# m219-bluetooth-input.net
KiCad netlist of a schematic drawn in EAGLE
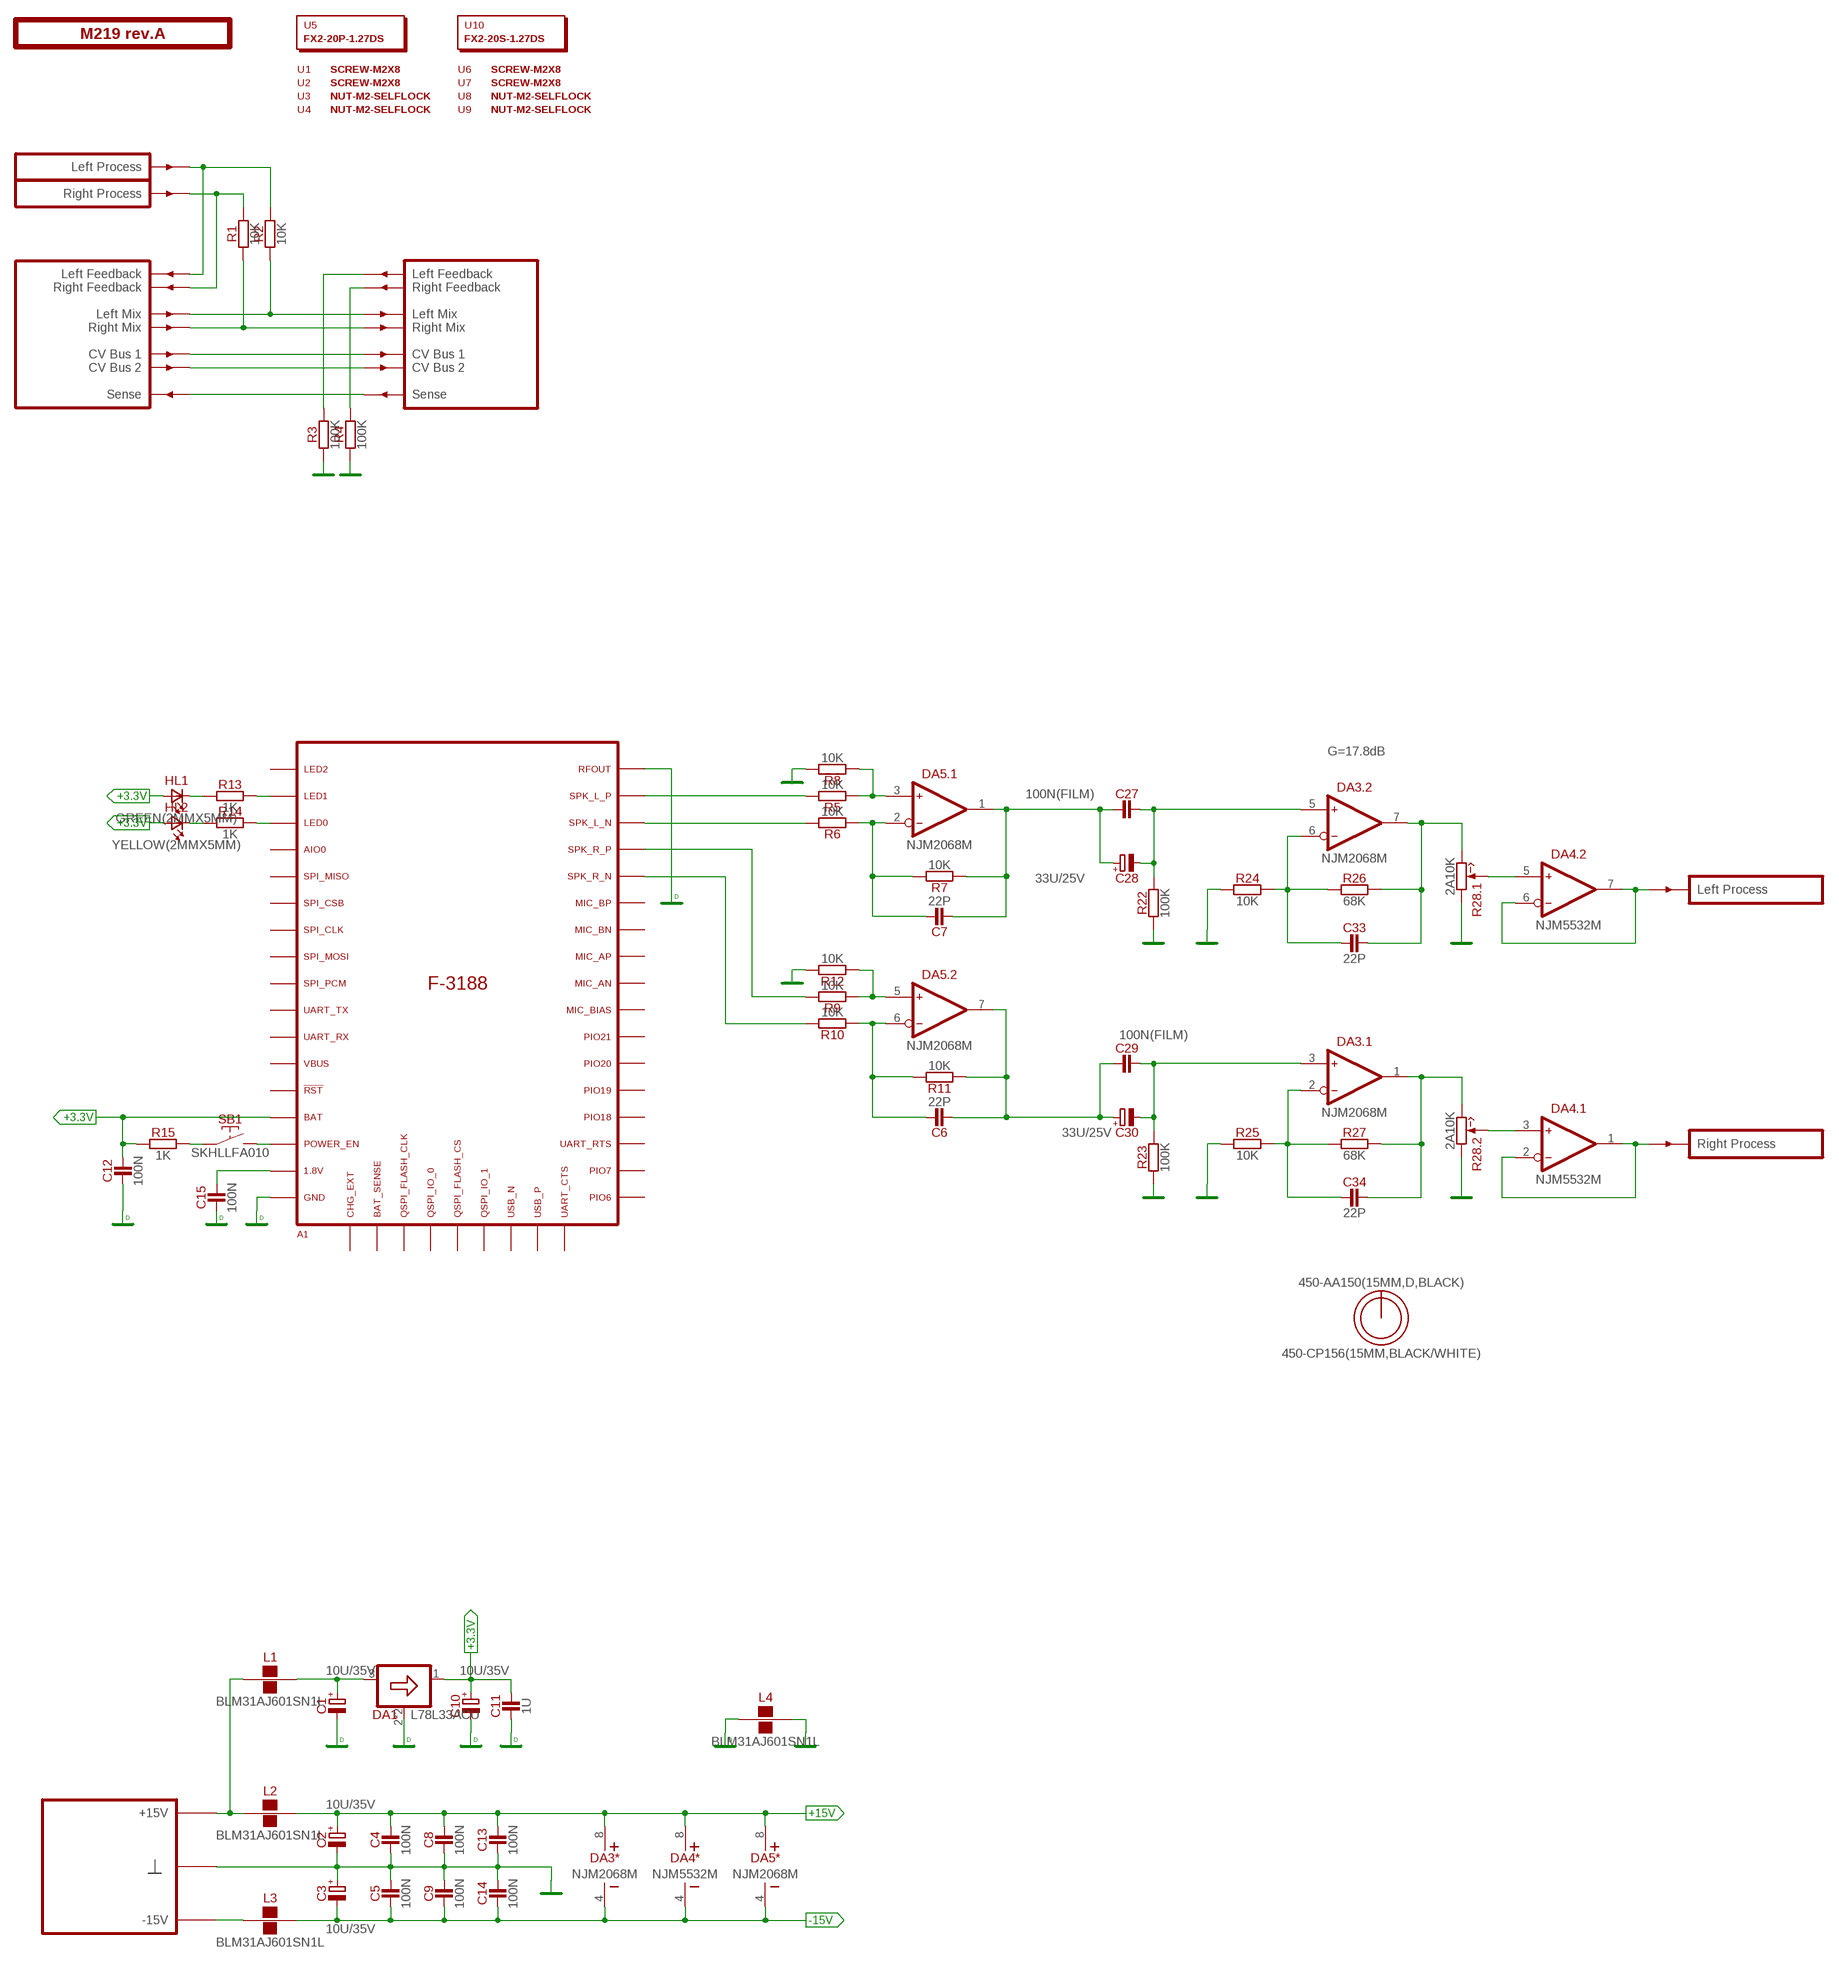
[diagram p0: schematic, sheet 1]

(export (version "E")
  (design (tool "Eeschema 10.0.6"))
  (components
    (comp (ref "A1")
      (value "F3188")
      (footprint "eagle-import:F3188")
      (libsource (lib "eagle-import") (part "F3188"))
    )
    (comp (ref "C1")
      (value "10U/35V")
      (footprint "eagle-import:E2-5")
      (libsource (lib "eagle-import") (part "?10U/35V"))
    )
    (comp (ref "C2")
      (value "10U/35V")
      (footprint "eagle-import:E2-5")
      (libsource (lib "eagle-import") (part "?10U/35V"))
    )
    (comp (ref "C3")
      (value "10U/35V")
      (footprint "eagle-import:E2-5")
      (libsource (lib "eagle-import") (part "?10U/35V"))
    )
    (comp (ref "C4")
      (value "100N")
      (footprint "eagle-import:C-0805")
      (libsource (lib "eagle-import") (part "?100N"))
    )
    (comp (ref "C5")
      (value "100N")
      (footprint "eagle-import:C-0805")
      (libsource (lib "eagle-import") (part "?100N"))
    )
    (comp (ref "C6")
      (value "22P")
      (footprint "eagle-import:C-0805")
      (libsource (lib "eagle-import") (part "?22P"))
    )
    (comp (ref "C7")
      (value "22P")
      (footprint "eagle-import:C-0805")
      (libsource (lib "eagle-import") (part "?22P"))
    )
    (comp (ref "C8")
      (value "100N")
      (footprint "eagle-import:C-0805")
      (libsource (lib "eagle-import") (part "?100N"))
    )
    (comp (ref "C9")
      (value "100N")
      (footprint "eagle-import:C-0805")
      (libsource (lib "eagle-import") (part "?100N"))
    )
    (comp (ref "C10")
      (value "10U/35V")
      (footprint "eagle-import:E2-5")
      (libsource (lib "eagle-import") (part "?10U/35V"))
    )
    (comp (ref "C11")
      (value "1U")
      (footprint "eagle-import:C-0805")
      (libsource (lib "eagle-import") (part "?1U"))
    )
    (comp (ref "C12")
      (value "100N")
      (footprint "eagle-import:C-0805")
      (libsource (lib "eagle-import") (part "?100N"))
    )
    (comp (ref "C13")
      (value "100N")
      (footprint "eagle-import:C-0805")
      (libsource (lib "eagle-import") (part "?100N"))
    )
    (comp (ref "C14")
      (value "100N")
      (footprint "eagle-import:C-0805")
      (libsource (lib "eagle-import") (part "?100N"))
    )
    (comp (ref "C15")
      (value "100N")
      (footprint "eagle-import:C-0805")
      (libsource (lib "eagle-import") (part "?100N"))
    )
    (comp (ref "C27")
      (value "100N(FILM)")
      (footprint "eagle-import:C050-025X075")
      (libsource (lib "eagle-import") (part "?100N(FILM)"))
    )
    (comp (ref "C28")
      (value "33U/25V")
      (footprint "eagle-import:E2,5-7")
      (libsource (lib "eagle-import") (part "?33U/25V"))
    )
    (comp (ref "C29")
      (value "100N(FILM)")
      (footprint "eagle-import:C050-025X075")
      (libsource (lib "eagle-import") (part "?100N(FILM)"))
    )
    (comp (ref "C30")
      (value "33U/25V")
      (footprint "eagle-import:E2,5-7")
      (libsource (lib "eagle-import") (part "?33U/25V"))
    )
    (comp (ref "C33")
      (value "22P")
      (footprint "eagle-import:C-0805")
      (libsource (lib "eagle-import") (part "?22P"))
    )
    (comp (ref "C34")
      (value "22P")
      (footprint "eagle-import:C-0805")
      (libsource (lib "eagle-import") (part "?22P"))
    )
    (comp (ref "DA1")
      (value "L78L33ACU")
      (footprint "eagle-import:SOT89")
      (libsource (lib "eagle-import") (part "?L78L33ACU"))
    )
    (comp (ref "DA3")
      (value "NJM2068M")
      (footprint "eagle-import:SO-8")
      (libsource (lib "eagle-import") (part "NJM2068M"))
    )
    (comp (ref "DA4")
      (value "NJM5532M")
      (footprint "eagle-import:SO-8")
      (libsource (lib "eagle-import") (part "NJM5532M"))
    )
    (comp (ref "DA5")
      (value "NJM2068M")
      (footprint "eagle-import:SO-8")
      (libsource (lib "eagle-import") (part "NJM2068M"))
    )
    (comp (ref "HL1")
      (value "GREEN(2MMX5MM)")
      (footprint "eagle-import:LED2X5")
      (libsource (lib "eagle-import") (part "?(2MMX5MM)GREEN"))
    )
    (comp (ref "HL2")
      (value "YELLOW(2MMX5MM)")
      (footprint "eagle-import:LED2X5")
      (libsource (lib "eagle-import") (part "?(2MMX5MM)YELLOW"))
    )
    (comp (ref "L1")
      (value "BLM31AJ601SN1L")
      (footprint "eagle-import:1206")
      (libsource (lib "eagle-import") (part "BLM31AJ601SN1L"))
    )
    (comp (ref "L2")
      (value "BLM31AJ601SN1L")
      (footprint "eagle-import:1206")
      (libsource (lib "eagle-import") (part "BLM31AJ601SN1L"))
    )
    (comp (ref "L3")
      (value "BLM31AJ601SN1L")
      (footprint "eagle-import:1206")
      (libsource (lib "eagle-import") (part "BLM31AJ601SN1L"))
    )
    (comp (ref "L4")
      (value "BLM31AJ601SN1L")
      (footprint "eagle-import:1206")
      (libsource (lib "eagle-import") (part "BLM31AJ601SN1L"))
    )
    (comp (ref "O1")
      (value "450-AA150(15MM,D,BLACK)")
      (footprint "eagle-import:EMPTY")
      (libsource (lib "eagle-import") (part "450-AA?150(15MM,D,BLACK)"))
    )
    (comp (ref "O2")
      (value "450-CP156(15MM,BLACK/WHITE)")
      (footprint "eagle-import:EMPTY")
      (libsource (lib "eagle-import") (part "450-C?P156(15MM,BLACK/WHITE)"))
    )
    (comp (ref "PCB1")
      (value "M219 rev.A")
      (footprint "eagle-import:ST2-BOARD-50")
      (libsource (lib "eagle-import") (part "ST2-BOARD-?50"))
    )
    (comp (ref "R1")
      (value "10K")
      (footprint "eagle-import:R-0805")
      (libsource (lib "eagle-import") (part "?10K"))
    )
    (comp (ref "R2")
      (value "10K")
      (footprint "eagle-import:R-0805")
      (libsource (lib "eagle-import") (part "?10K"))
    )
    (comp (ref "R3")
      (value "100K")
      (footprint "eagle-import:R-0805")
      (libsource (lib "eagle-import") (part "?100K"))
    )
    (comp (ref "R4")
      (value "100K")
      (footprint "eagle-import:R-0805")
      (libsource (lib "eagle-import") (part "?100K"))
    )
    (comp (ref "R5")
      (value "10K")
      (footprint "eagle-import:R-0805")
      (libsource (lib "eagle-import") (part "?10K"))
    )
    (comp (ref "R6")
      (value "10K")
      (footprint "eagle-import:R-0805")
      (libsource (lib "eagle-import") (part "?10K"))
    )
    (comp (ref "R7")
      (value "10K")
      (footprint "eagle-import:R-0805")
      (libsource (lib "eagle-import") (part "?10K"))
    )
    (comp (ref "R8")
      (value "10K")
      (footprint "eagle-import:R-0805")
      (libsource (lib "eagle-import") (part "?10K"))
    )
    (comp (ref "R9")
      (value "10K")
      (footprint "eagle-import:R-0805")
      (libsource (lib "eagle-import") (part "?10K"))
    )
    (comp (ref "R10")
      (value "10K")
      (footprint "eagle-import:R-0805")
      (libsource (lib "eagle-import") (part "?10K"))
    )
    (comp (ref "R11")
      (value "10K")
      (footprint "eagle-import:R-0805")
      (libsource (lib "eagle-import") (part "?10K"))
    )
    (comp (ref "R12")
      (value "10K")
      (footprint "eagle-import:R-0805")
      (libsource (lib "eagle-import") (part "?10K"))
    )
    (comp (ref "R13")
      (value "1K")
      (footprint "eagle-import:R-0805")
      (libsource (lib "eagle-import") (part "?1K"))
    )
    (comp (ref "R14")
      (value "1K")
      (footprint "eagle-import:R-0805")
      (libsource (lib "eagle-import") (part "?1K"))
    )
    (comp (ref "R15")
      (value "1K")
      (footprint "eagle-import:R-0805")
      (libsource (lib "eagle-import") (part "?1K"))
    )
    (comp (ref "R22")
      (value "100K")
      (footprint "eagle-import:R-0805")
      (libsource (lib "eagle-import") (part "?100K"))
    )
    (comp (ref "R23")
      (value "100K")
      (footprint "eagle-import:R-0805")
      (libsource (lib "eagle-import") (part "?100K"))
    )
    (comp (ref "R24")
      (value "10K")
      (footprint "eagle-import:R-0805")
      (libsource (lib "eagle-import") (part "?10K"))
    )
    (comp (ref "R25")
      (value "10K")
      (footprint "eagle-import:R-0805")
      (libsource (lib "eagle-import") (part "?10K"))
    )
    (comp (ref "R26")
      (value "68K")
      (footprint "eagle-import:R-0805")
      (libsource (lib "eagle-import") (part "?68K"))
    )
    (comp (ref "R27")
      (value "68K")
      (footprint "eagle-import:R-0805")
      (libsource (lib "eagle-import") (part "?68K"))
    )
    (comp (ref "R28")
      (value "2A10K")
      (footprint "eagle-import:RV11-DUAL")
      (libsource (lib "eagle-import") (part "2?A10K"))
    )
    (comp (ref "SB1")
      (value "SKHLLFA010")
      (footprint "eagle-import:SKHLLFA010")
      (libsource (lib "eagle-import") (part "SKHLLFA010"))
    )
    (comp (ref "U1")
      (value "SCREW-M2X8")
      (footprint "eagle-import:EMPTY")
      (libsource (lib "eagle-import") (part "?SCREW-M2X8"))
    )
    (comp (ref "U2")
      (value "SCREW-M2X8")
      (footprint "eagle-import:EMPTY")
      (libsource (lib "eagle-import") (part "?SCREW-M2X8"))
    )
    (comp (ref "U3")
      (value "NUT-M2-SELFLOCK")
      (footprint "eagle-import:EMPTY")
      (libsource (lib "eagle-import") (part "?NUT-M2-SELFLOCK"))
    )
    (comp (ref "U4")
      (value "NUT-M2-SELFLOCK")
      (footprint "eagle-import:EMPTY")
      (libsource (lib "eagle-import") (part "?NUT-M2-SELFLOCK"))
    )
    (comp (ref "U5")
      (value "FX2-20P-1.27DS")
      (footprint "eagle-import:EMPTY")
      (libsource (lib "eagle-import") (part "?FX2-20P-1.27DS"))
    )
    (comp (ref "U6")
      (value "SCREW-M2X8")
      (footprint "eagle-import:EMPTY")
      (libsource (lib "eagle-import") (part "?SCREW-M2X8"))
    )
    (comp (ref "U7")
      (value "SCREW-M2X8")
      (footprint "eagle-import:EMPTY")
      (libsource (lib "eagle-import") (part "?SCREW-M2X8"))
    )
    (comp (ref "U8")
      (value "NUT-M2-SELFLOCK")
      (footprint "eagle-import:EMPTY")
      (libsource (lib "eagle-import") (part "?NUT-M2-SELFLOCK"))
    )
    (comp (ref "U9")
      (value "NUT-M2-SELFLOCK")
      (footprint "eagle-import:EMPTY")
      (libsource (lib "eagle-import") (part "?NUT-M2-SELFLOCK"))
    )
    (comp (ref "U10")
      (value "FX2-20S-1.27DS")
      (footprint "eagle-import:EMPTY")
      (libsource (lib "eagle-import") (part "?FX2-20S-1.27DS"))
    )
  )
  (nets
    (net (code "1") (name "+3.3V") (class "Default")
      (node (ref "A1") (pin "P$14") (pinfunction "BAT_P$14") (pintype "power_in"))
      (node (ref "C10") (pin "+") (pinfunction "+_+") (pintype "passive"))
      (node (ref "C11") (pin "2") (pinfunction "2_2") (pintype "passive"))
      (node (ref "C12") (pin "2") (pinfunction "2_2") (pintype "passive"))
      (node (ref "DA1") (pin "1") (pinfunction "OUT_1") (pintype "power_in"))
      (node (ref "HL1") (pin "A") (pinfunction "A_A") (pintype "passive"))
      (node (ref "HL2") (pin "A") (pinfunction "A_A") (pintype "passive"))
      (node (ref "R15") (pin "1") (pinfunction "1_1") (pintype "passive"))
    )
    (net (code "2") (name "+15V") (class "Default")
      (node (ref "C13") (pin "2") (pinfunction "2_2") (pintype "passive"))
      (node (ref "C2") (pin "+") (pinfunction "+_+") (pintype "passive"))
      (node (ref "C4") (pin "2") (pinfunction "2_2") (pintype "passive"))
      (node (ref "C8") (pin "2") (pinfunction "2_2") (pintype "passive"))
      (node (ref "DA3") (pin "8") (pinfunction "V+_8") (pintype "power_in"))
      (node (ref "DA4") (pin "8") (pinfunction "V+_8") (pintype "power_in"))
      (node (ref "DA5") (pin "8") (pinfunction "V+_8") (pintype "power_in"))
      (node (ref "L2") (pin "2") (pinfunction "2_2") (pintype "passive"))
    )
    (net (code "3") (name "-15V") (class "Default")
      (node (ref "C14") (pin "1") (pinfunction "1_1") (pintype "passive"))
      (node (ref "C3") (pin "-") (pinfunction "-_-") (pintype "passive"))
      (node (ref "C5") (pin "1") (pinfunction "1_1") (pintype "passive"))
      (node (ref "C9") (pin "1") (pinfunction "1_1") (pintype "passive"))
      (node (ref "DA3") (pin "4") (pinfunction "V-_4") (pintype "power_in"))
      (node (ref "DA4") (pin "4") (pinfunction "V-_4") (pintype "power_in"))
      (node (ref "DA5") (pin "4") (pinfunction "V-_4") (pintype "power_in"))
      (node (ref "L3") (pin "2") (pinfunction "2_2") (pintype "passive"))
    )
    (net (code "4") (name "/VBUS") (class "Default")
      (node (ref "A1") (pin "P$12") (pinfunction "VBUS_P$12") (pintype "power_in"))
    )
    (net (code "5") (name "DGND") (class "Default")
      (node (ref "A1") (pin "P$17") (pinfunction "GND_P$17") (pintype "power_in"))
      (node (ref "A1") (pin "P$43") (pinfunction "RFOUT_P$43") (pintype "bidirectional"))
      (node (ref "C1") (pin "-") (pinfunction "-_-") (pintype "passive"))
      (node (ref "C10") (pin "-") (pinfunction "-_-") (pintype "passive"))
      (node (ref "C11") (pin "1") (pinfunction "1_1") (pintype "passive"))
      (node (ref "C12") (pin "1") (pinfunction "1_1") (pintype "passive"))
      (node (ref "C15") (pin "1") (pinfunction "1_1") (pintype "passive"))
      (node (ref "DA1") (pin "2") (pinfunction "GND_2") (pintype "power_in"))
      (node (ref "DA1") (pin "2@1") (pinfunction "GND_2@1") (pintype "power_in"))
      (node (ref "L4") (pin "1") (pinfunction "1_1") (pintype "passive"))
    )
    (net (code "6") (name "GND") (class "Default")
      (node (ref "C13") (pin "1") (pinfunction "1_1") (pintype "passive"))
      (node (ref "C14") (pin "2") (pinfunction "2_2") (pintype "passive"))
      (node (ref "C2") (pin "-") (pinfunction "-_-") (pintype "passive"))
      (node (ref "C3") (pin "+") (pinfunction "+_+") (pintype "passive"))
      (node (ref "C4") (pin "1") (pinfunction "1_1") (pintype "passive"))
      (node (ref "C5") (pin "2") (pinfunction "2_2") (pintype "passive"))
      (node (ref "C8") (pin "1") (pinfunction "1_1") (pintype "passive"))
      (node (ref "C9") (pin "2") (pinfunction "2_2") (pintype "passive"))
      (node (ref "L4") (pin "2") (pinfunction "2_2") (pintype "passive"))
      (node (ref "PCB1") (pin "B4") (pinfunction "GND_B4") (pintype "bidirectional"))
      (node (ref "PCB1") (pin "B4'") (pinfunction "GND_B4'") (pintype "bidirectional"))
      (node (ref "PCB1") (pin "B5") (pinfunction "GND_B5") (pintype "bidirectional"))
      (node (ref "PCB1") (pin "B5'") (pinfunction "GND_B5'") (pintype "bidirectional"))
      (node (ref "PCB1") (pin "B6") (pinfunction "GND_B6") (pintype "bidirectional"))
      (node (ref "PCB1") (pin "B6'") (pinfunction "GND_B6'") (pintype "bidirectional"))
      (node (ref "PCB1") (pin "B7") (pinfunction "GND_B7") (pintype "bidirectional"))
      (node (ref "PCB1") (pin "B7'") (pinfunction "GND_B7'") (pintype "bidirectional"))
      (node (ref "PCB1") (pin "B8") (pinfunction "GND_B8") (pintype "bidirectional"))
      (node (ref "PCB1") (pin "B8'") (pinfunction "GND_B8'") (pintype "bidirectional"))
      (node (ref "R12") (pin "1") (pinfunction "1_1") (pintype "passive"))
      (node (ref "R22") (pin "1") (pinfunction "1_1") (pintype "passive"))
      (node (ref "R23") (pin "1") (pinfunction "1_1") (pintype "passive"))
      (node (ref "R24") (pin "1") (pinfunction "1_1") (pintype "passive"))
      (node (ref "R25") (pin "1") (pinfunction "1_1") (pintype "passive"))
      (node (ref "R28") (pin "1") (pinfunction "CCW_1") (pintype "passive"))
      (node (ref "R28") (pin "1'") (pinfunction "CCW_1'") (pintype "passive"))
      (node (ref "R3") (pin "1") (pinfunction "1_1") (pintype "passive"))
      (node (ref "R4") (pin "1") (pinfunction "1_1") (pintype "passive"))
      (node (ref "R8") (pin "1") (pinfunction "1_1") (pintype "passive"))
    )
    (net (code "7") (name "Net-(A1-LED0)") (class "Default")
      (node (ref "A1") (pin "P$3") (pinfunction "LED0_P$3") (pintype "bidirectional"))
      (node (ref "R14") (pin "2") (pinfunction "2_2") (pintype "passive"))
    )
    (net (code "8") (name "Net-(A1-LED1)") (class "Default")
      (node (ref "A1") (pin "P$2") (pinfunction "LED1_P$2") (pintype "bidirectional"))
      (node (ref "R13") (pin "2") (pinfunction "2_2") (pintype "passive"))
    )
    (net (code "9") (name "Net-(A1-POWER_EN)") (class "Default")
      (node (ref "A1") (pin "P$15") (pinfunction "POWER_EN_P$15") (pintype "bidirectional"))
      (node (ref "SB1") (pin "2") (pinfunction "2_2") (pintype "passive"))
    )
    (net (code "10") (name "Net-(A1-SPK_L_N1)") (class "Default")
      (node (ref "A1") (pin "P$41") (pinfunction "SPK_L_N1_P$41") (pintype "bidirectional"))
      (node (ref "R6") (pin "1") (pinfunction "1_1") (pintype "passive"))
    )
    (net (code "11") (name "Net-(A1-SPK_L_P1)") (class "Default")
      (node (ref "A1") (pin "P$42") (pinfunction "SPK_L_P1_P$42") (pintype "bidirectional"))
      (node (ref "R5") (pin "1") (pinfunction "1_1") (pintype "passive"))
    )
    (net (code "12") (name "Net-(A1-SPK_R_N1)") (class "Default")
      (node (ref "A1") (pin "P$39") (pinfunction "SPK_R_N1_P$39") (pintype "bidirectional"))
      (node (ref "R10") (pin "1") (pinfunction "1_1") (pintype "passive"))
    )
    (net (code "13") (name "Net-(A1-SPK_R_P1)") (class "Default")
      (node (ref "A1") (pin "P$40") (pinfunction "SPK_R_P1_P$40") (pintype "bidirectional"))
      (node (ref "R9") (pin "1") (pinfunction "1_1") (pintype "passive"))
    )
    (net (code "14") (name "Net-(A1-VBUS_1.8V)") (class "Default")
      (node (ref "A1") (pin "P$16") (pinfunction "VBUS_1.8V_P$16") (pintype "power_in"))
      (node (ref "C15") (pin "2") (pinfunction "2_2") (pintype "passive"))
    )
    (net (code "15") (name "Net-(DA1-IN)") (class "Default")
      (node (ref "C1") (pin "+") (pinfunction "+_+") (pintype "passive"))
      (node (ref "DA1") (pin "3") (pinfunction "IN_3") (pintype "power_in"))
      (node (ref "L1") (pin "2") (pinfunction "2_2") (pintype "passive"))
    )
    (net (code "16") (name "Net-(DA3B-IN+)") (class "Default")
      (node (ref "C29") (pin "2") (pinfunction "2_2") (pintype "passive"))
      (node (ref "C30") (pin "-") (pinfunction "-_-") (pintype "passive"))
      (node (ref "DA3") (pin "3") (pinfunction "IN+_3") (pintype "input"))
      (node (ref "R23") (pin "2") (pinfunction "2_2") (pintype "passive"))
    )
    (net (code "17") (name "Net-(DA3B-IN-)") (class "Default")
      (node (ref "C34") (pin "1") (pinfunction "1_1") (pintype "passive"))
      (node (ref "DA3") (pin "2") (pinfunction "IN-_2") (pintype "input"))
      (node (ref "R25") (pin "2") (pinfunction "2_2") (pintype "passive"))
      (node (ref "R27") (pin "1") (pinfunction "1_1") (pintype "passive"))
    )
    (net (code "18") (name "Net-(DA3B-OUT)") (class "Default")
      (node (ref "C34") (pin "2") (pinfunction "2_2") (pintype "passive"))
      (node (ref "DA3") (pin "1") (pinfunction "OUT_1") (pintype "output"))
      (node (ref "R27") (pin "2") (pinfunction "2_2") (pintype "passive"))
      (node (ref "R28") (pin "3'") (pinfunction "CW_3'") (pintype "passive"))
    )
    (net (code "19") (name "Net-(DA3C-IN+)") (class "Default")
      (node (ref "C27") (pin "2") (pinfunction "2_2") (pintype "passive"))
      (node (ref "C28") (pin "-") (pinfunction "-_-") (pintype "passive"))
      (node (ref "DA3") (pin "5") (pinfunction "IN+_5") (pintype "input"))
      (node (ref "R22") (pin "2") (pinfunction "2_2") (pintype "passive"))
    )
    (net (code "20") (name "Net-(DA3C-IN-)") (class "Default")
      (node (ref "C33") (pin "1") (pinfunction "1_1") (pintype "passive"))
      (node (ref "DA3") (pin "6") (pinfunction "IN-_6") (pintype "input"))
      (node (ref "R24") (pin "2") (pinfunction "2_2") (pintype "passive"))
      (node (ref "R26") (pin "1") (pinfunction "1_1") (pintype "passive"))
    )
    (net (code "21") (name "Net-(DA3C-OUT)") (class "Default")
      (node (ref "C33") (pin "2") (pinfunction "2_2") (pintype "passive"))
      (node (ref "DA3") (pin "7") (pinfunction "OUT_7") (pintype "output"))
      (node (ref "R26") (pin "2") (pinfunction "2_2") (pintype "passive"))
      (node (ref "R28") (pin "3") (pinfunction "CW_3") (pintype "passive"))
    )
    (net (code "22") (name "Net-(DA4B-IN+)") (class "Default")
      (node (ref "DA4") (pin "3") (pinfunction "IN+_3") (pintype "input"))
      (node (ref "R28") (pin "2'") (pinfunction "W_2'") (pintype "passive"))
    )
    (net (code "23") (name "Net-(DA4B-IN-)") (class "Default")
      (node (ref "DA4") (pin "1") (pinfunction "OUT_1") (pintype "output"))
      (node (ref "DA4") (pin "2") (pinfunction "IN-_2") (pintype "input"))
      (node (ref "PCB1") (pin "BOUTR'") (pinfunction "OUTR_BOUTR'") (pintype "bidirectional"))
    )
    (net (code "24") (name "Net-(DA4C-IN+)") (class "Default")
      (node (ref "DA4") (pin "5") (pinfunction "IN+_5") (pintype "input"))
      (node (ref "R28") (pin "2") (pinfunction "W_2") (pintype "passive"))
    )
    (net (code "25") (name "Net-(DA4C-IN-)") (class "Default")
      (node (ref "DA4") (pin "6") (pinfunction "IN-_6") (pintype "input"))
      (node (ref "DA4") (pin "7") (pinfunction "OUT_7") (pintype "output"))
      (node (ref "PCB1") (pin "BOUTL'") (pinfunction "OUTL_BOUTL'") (pintype "bidirectional"))
    )
    (net (code "26") (name "Net-(DA5B-IN+)") (class "Default")
      (node (ref "DA5") (pin "3") (pinfunction "IN+_3") (pintype "input"))
      (node (ref "R5") (pin "2") (pinfunction "2_2") (pintype "passive"))
      (node (ref "R8") (pin "2") (pinfunction "2_2") (pintype "passive"))
    )
    (net (code "27") (name "Net-(DA5B-IN-)") (class "Default")
      (node (ref "C7") (pin "1") (pinfunction "1_1") (pintype "passive"))
      (node (ref "DA5") (pin "2") (pinfunction "IN-_2") (pintype "input"))
      (node (ref "R6") (pin "2") (pinfunction "2_2") (pintype "passive"))
      (node (ref "R7") (pin "1") (pinfunction "1_1") (pintype "passive"))
    )
    (net (code "28") (name "Net-(DA5B-OUT)") (class "Default")
      (node (ref "C27") (pin "1") (pinfunction "1_1") (pintype "passive"))
      (node (ref "C28") (pin "+") (pinfunction "+_+") (pintype "passive"))
      (node (ref "C7") (pin "2") (pinfunction "2_2") (pintype "passive"))
      (node (ref "DA5") (pin "1") (pinfunction "OUT_1") (pintype "output"))
      (node (ref "R7") (pin "2") (pinfunction "2_2") (pintype "passive"))
    )
    (net (code "29") (name "Net-(DA5C-IN+)") (class "Default")
      (node (ref "DA5") (pin "5") (pinfunction "IN+_5") (pintype "input"))
      (node (ref "R12") (pin "2") (pinfunction "2_2") (pintype "passive"))
      (node (ref "R9") (pin "2") (pinfunction "2_2") (pintype "passive"))
    )
    (net (code "30") (name "Net-(DA5C-IN-)") (class "Default")
      (node (ref "C6") (pin "1") (pinfunction "1_1") (pintype "passive"))
      (node (ref "DA5") (pin "6") (pinfunction "IN-_6") (pintype "input"))
      (node (ref "R10") (pin "2") (pinfunction "2_2") (pintype "passive"))
      (node (ref "R11") (pin "1") (pinfunction "1_1") (pintype "passive"))
    )
    (net (code "31") (name "Net-(DA5C-OUT)") (class "Default")
      (node (ref "C29") (pin "1") (pinfunction "1_1") (pintype "passive"))
      (node (ref "C30") (pin "+") (pinfunction "+_+") (pintype "passive"))
      (node (ref "C6") (pin "2") (pinfunction "2_2") (pintype "passive"))
      (node (ref "DA5") (pin "7") (pinfunction "OUT_7") (pintype "output"))
      (node (ref "R11") (pin "2") (pinfunction "2_2") (pintype "passive"))
    )
    (net (code "32") (name "Net-(HL1-C)") (class "Default")
      (node (ref "HL1") (pin "K") (pinfunction "C_K") (pintype "passive"))
      (node (ref "R13") (pin "1") (pinfunction "1_1") (pintype "passive"))
    )
    (net (code "33") (name "Net-(HL2-C)") (class "Default")
      (node (ref "HL2") (pin "K") (pinfunction "C_K") (pintype "passive"))
      (node (ref "R14") (pin "1") (pinfunction "1_1") (pintype "passive"))
    )
    (net (code "34") (name "Net-(L1-Pad1)") (class "Default")
      (node (ref "L1") (pin "1") (pinfunction "1_1") (pintype "passive"))
      (node (ref "L2") (pin "1") (pinfunction "1_1") (pintype "passive"))
      (node (ref "PCB1") (pin "A+15") (pinfunction "P+15V_A+15") (pintype "bidirectional"))
      (node (ref "PCB1") (pin "A+15'") (pinfunction "P+15V_A+15'") (pintype "bidirectional"))
      (node (ref "PCB1") (pin "B+15") (pinfunction "P+15V_B+15") (pintype "bidirectional"))
      (node (ref "PCB1") (pin "B+15'") (pinfunction "P+15V_B+15'") (pintype "bidirectional"))
    )
    (net (code "35") (name "Net-(L3-Pad1)") (class "Default")
      (node (ref "L3") (pin "1") (pinfunction "1_1") (pintype "passive"))
      (node (ref "PCB1") (pin "A-15") (pinfunction "P-15V_A-15") (pintype "bidirectional"))
      (node (ref "PCB1") (pin "A-15'") (pinfunction "P-15V_A-15'") (pintype "bidirectional"))
      (node (ref "PCB1") (pin "B-15") (pinfunction "P-15V_B-15") (pintype "bidirectional"))
      (node (ref "PCB1") (pin "B-15'") (pinfunction "P-15V_B-15'") (pintype "bidirectional"))
    )
    (net (code "36") (name "Net-(PCB1B-INL)") (class "Default")
      (node (ref "PCB1") (pin "ALFBK") (pinfunction "LFBK_ALFBK") (pintype "bidirectional"))
      (node (ref "PCB1") (pin "BINL") (pinfunction "INL_BINL") (pintype "bidirectional"))
      (node (ref "R2") (pin "2") (pinfunction "2_2") (pintype "passive"))
    )
    (net (code "37") (name "Net-(PCB1C-INR)") (class "Default")
      (node (ref "PCB1") (pin "ARFBK") (pinfunction "RFBK_ARFBK") (pintype "bidirectional"))
      (node (ref "PCB1") (pin "BINR") (pinfunction "INR_BINR") (pintype "bidirectional"))
      (node (ref "R1") (pin "2") (pinfunction "2_2") (pintype "passive"))
    )
    (net (code "38") (name "Net-(PCB1F-CV1)") (class "Default")
      (node (ref "PCB1") (pin "ACV1") (pinfunction "CV1_ACV1") (pintype "bidirectional"))
      (node (ref "PCB1") (pin "ACV1'") (pinfunction "CV1'_ACV1'") (pintype "bidirectional"))
    )
    (net (code "39") (name "Net-(PCB1F-CV2)") (class "Default")
      (node (ref "PCB1") (pin "ACV2") (pinfunction "CV2_ACV2") (pintype "bidirectional"))
      (node (ref "PCB1") (pin "ACV2'") (pinfunction "CV2'_ACV2'") (pintype "bidirectional"))
    )
    (net (code "40") (name "Net-(PCB1F-LMIX)") (class "Default")
      (node (ref "PCB1") (pin "ALMIX") (pinfunction "LMIX_ALMIX") (pintype "bidirectional"))
      (node (ref "PCB1") (pin "ALMIX'") (pinfunction "LMIX'_ALMIX'") (pintype "bidirectional"))
      (node (ref "R2") (pin "1") (pinfunction "1_1") (pintype "passive"))
    )
    (net (code "41") (name "Net-(PCB1F-RMIX)") (class "Default")
      (node (ref "PCB1") (pin "ARMIX") (pinfunction "RMIX_ARMIX") (pintype "bidirectional"))
      (node (ref "PCB1") (pin "ARMIX'") (pinfunction "RMIX'_ARMIX'") (pintype "bidirectional"))
      (node (ref "R1") (pin "1") (pinfunction "1_1") (pintype "passive"))
    )
    (net (code "42") (name "Net-(PCB1F-SENSE)") (class "Default")
      (node (ref "PCB1") (pin "BSENSE") (pinfunction "SENSE_BSENSE") (pintype "bidirectional"))
      (node (ref "PCB1") (pin "BSENSE'") (pinfunction "SENSE'_BSENSE'") (pintype "bidirectional"))
    )
    (net (code "43") (name "Net-(PCB1G-LFBK')") (class "Default")
      (node (ref "PCB1") (pin "ALFBK'") (pinfunction "LFBK'_ALFBK'") (pintype "bidirectional"))
      (node (ref "R3") (pin "2") (pinfunction "2_2") (pintype "passive"))
    )
    (net (code "44") (name "Net-(PCB1G-RFBK')") (class "Default")
      (node (ref "PCB1") (pin "ARFBK'") (pinfunction "RFBK'_ARFBK'") (pintype "bidirectional"))
      (node (ref "R4") (pin "2") (pinfunction "2_2") (pintype "passive"))
    )
    (net (code "45") (name "Net-(R15-Pad2)") (class "Default")
      (node (ref "R15") (pin "2") (pinfunction "2_2") (pintype "passive"))
      (node (ref "SB1") (pin "1") (pinfunction "1_1") (pintype "passive"))
    )
    (net (code "46") (name "unconnected-(A1-AIO0-PadP$4)") (class "Default")
      (node (ref "A1") (pin "P$4") (pinfunction "AIO0_P$4") (pintype "bidirectional"))
    )
    (net (code "47") (name "unconnected-(A1-BAT_SENSE-PadP$19)") (class "Default")
      (node (ref "A1") (pin "P$19") (pinfunction "BAT_SENSE_P$19") (pintype "bidirectional"))
    )
    (net (code "48") (name "unconnected-(A1-CHG_EXT-PadP$18)") (class "Default")
      (node (ref "A1") (pin "P$18") (pinfunction "CHG_EXT_P$18") (pintype "bidirectional"))
    )
    (net (code "49") (name "unconnected-(A1-LED2-PadP$1)") (class "Default")
      (node (ref "A1") (pin "P$1") (pinfunction "LED2_P$1") (pintype "bidirectional"))
    )
    (net (code "50") (name "unconnected-(A1-MIC_AN-PadP$35)") (class "Default")
      (node (ref "A1") (pin "P$35") (pinfunction "MIC_AN_P$35") (pintype "bidirectional"))
    )
    (net (code "51") (name "unconnected-(A1-MIC_AP-PadP$36)") (class "Default")
      (node (ref "A1") (pin "P$36") (pinfunction "MIC_AP_P$36") (pintype "bidirectional"))
    )
    (net (code "52") (name "unconnected-(A1-MIC_BIAS-PadP$34)") (class "Default")
      (node (ref "A1") (pin "P$34") (pinfunction "MIC_BIAS_P$34") (pintype "bidirectional"))
    )
    (net (code "53") (name "unconnected-(A1-MIC_BN-PadP$37)") (class "Default")
      (node (ref "A1") (pin "P$37") (pinfunction "MIC_BN_P$37") (pintype "bidirectional"))
    )
    (net (code "54") (name "unconnected-(A1-MIC_BP-PadP$38)") (class "Default")
      (node (ref "A1") (pin "P$38") (pinfunction "MIC_BP_P$38") (pintype "bidirectional"))
    )
    (net (code "55") (name "unconnected-(A1-PIO6-PadP$27)") (class "Default")
      (node (ref "A1") (pin "P$27") (pinfunction "PIO6_P$27") (pintype "bidirectional"))
    )
    (net (code "56") (name "unconnected-(A1-PIO7-PadP$28)") (class "Default")
      (node (ref "A1") (pin "P$28") (pinfunction "PIO7_P$28") (pintype "bidirectional"))
    )
    (net (code "57") (name "unconnected-(A1-PIO8{slash}UART_RTS-PadP$29)") (class "Default")
      (node (ref "A1") (pin "P$29") (pinfunction "PIO8/UART_RTS_P$29") (pintype "bidirectional"))
    )
    (net (code "58") (name "unconnected-(A1-PIO9{slash}UART_CTS-PadP$26)") (class "Default")
      (node (ref "A1") (pin "P$26") (pinfunction "PIO9/UART_CTS_P$26") (pintype "bidirectional"))
    )
    (net (code "59") (name "unconnected-(A1-PIO10{slash}QSPI_FLASH_CLK-PadP$20)") (class "Default")
      (node (ref "A1") (pin "P$20") (pinfunction "PIO10/QSPI_FLASH_CLK_P$20") (pintype "bidirectional"))
    )
    (net (code "60") (name "unconnected-(A1-PIO11{slash}QSPI_IO_0-PadP$21)") (class "Default")
      (node (ref "A1") (pin "P$21") (pinfunction "PIO11/QSPI_IO_0_P$21") (pintype "bidirectional"))
    )
    (net (code "61") (name "unconnected-(A1-PIO12{slash}QSPI_FLASH_CS-PadP$22)") (class "Default")
      (node (ref "A1") (pin "P$22") (pinfunction "PIO12/QSPI_FLASH_CS_P$22") (pintype "bidirectional"))
    )
    (net (code "62") (name "unconnected-(A1-PIO13{slash}QSPI_IO_1-PadP$23)") (class "Default")
      (node (ref "A1") (pin "P$23") (pinfunction "PIO13/QSPI_IO_1_P$23") (pintype "bidirectional"))
    )
    (net (code "63") (name "unconnected-(A1-PIO18-PadP$30)") (class "Default")
      (node (ref "A1") (pin "P$30") (pinfunction "PIO18_P$30") (pintype "bidirectional"))
    )
    (net (code "64") (name "unconnected-(A1-PIO19-PadP$31)") (class "Default")
      (node (ref "A1") (pin "P$31") (pinfunction "PIO19_P$31") (pintype "bidirectional"))
    )
    (net (code "65") (name "unconnected-(A1-PIO20-PadP$32)") (class "Default")
      (node (ref "A1") (pin "P$32") (pinfunction "PIO20_P$32") (pintype "bidirectional"))
    )
    (net (code "66") (name "unconnected-(A1-PIO21-PadP$33)") (class "Default")
      (node (ref "A1") (pin "P$33") (pinfunction "PIO21_P$33") (pintype "bidirectional"))
    )
    (net (code "67") (name "unconnected-(A1-RST#-PadP$13)") (class "Default")
      (node (ref "A1") (pin "P$13") (pinfunction "RST#_P$13") (pintype "bidirectional"))
    )
    (net (code "68") (name "unconnected-(A1-SPI_CLK{slash}PIO5-PadP$7)") (class "Default")
      (node (ref "A1") (pin "P$7") (pinfunction "SPI_CLK/PIO5_P$7") (pintype "bidirectional"))
    )
    (net (code "69") (name "unconnected-(A1-SPI_CSB{slash}PIO4-PadP$6)") (class "Default")
      (node (ref "A1") (pin "P$6") (pinfunction "SPI_CSB/PIO4_P$6") (pintype "bidirectional"))
    )
    (net (code "70") (name "unconnected-(A1-SPI_MISO{slash}PIO3-PadP$5)") (class "Default")
      (node (ref "A1") (pin "P$5") (pinfunction "SPI_MISO/PIO3_P$5") (pintype "bidirectional"))
    )
    (net (code "71") (name "unconnected-(A1-SPI_MOSI{slash}PIO2-PadP$8)") (class "Default")
      (node (ref "A1") (pin "P$8") (pinfunction "SPI_MOSI/PIO2_P$8") (pintype "bidirectional"))
    )
    (net (code "72") (name "unconnected-(A1-SPI_PCM-PadP$9)") (class "Default")
      (node (ref "A1") (pin "P$9") (pinfunction "SPI_PCM_P$9") (pintype "bidirectional"))
    )
    (net (code "73") (name "unconnected-(A1-UART_RX{slash}PIO0-PadP$11)") (class "Default")
      (node (ref "A1") (pin "P$11") (pinfunction "UART_RX/PIO0_P$11") (pintype "bidirectional"))
    )
    (net (code "74") (name "unconnected-(A1-UART_TX{slash}PIO1-PadP$10)") (class "Default")
      (node (ref "A1") (pin "P$10") (pinfunction "UART_TX/PIO1_P$10") (pintype "bidirectional"))
    )
    (net (code "75") (name "unconnected-(A1-USB_N-PadP$24)") (class "Default")
      (node (ref "A1") (pin "P$24") (pinfunction "USB_N_P$24") (pintype "bidirectional"))
    )
    (net (code "76") (name "unconnected-(A1-USB_P-PadP$25)") (class "Default")
      (node (ref "A1") (pin "P$25") (pinfunction "USB_P_P$25") (pintype "bidirectional"))
    )
  )
)
